# ESP8266_ESP12.net
KiCad netlist of a schematic drawn in Altium Designer
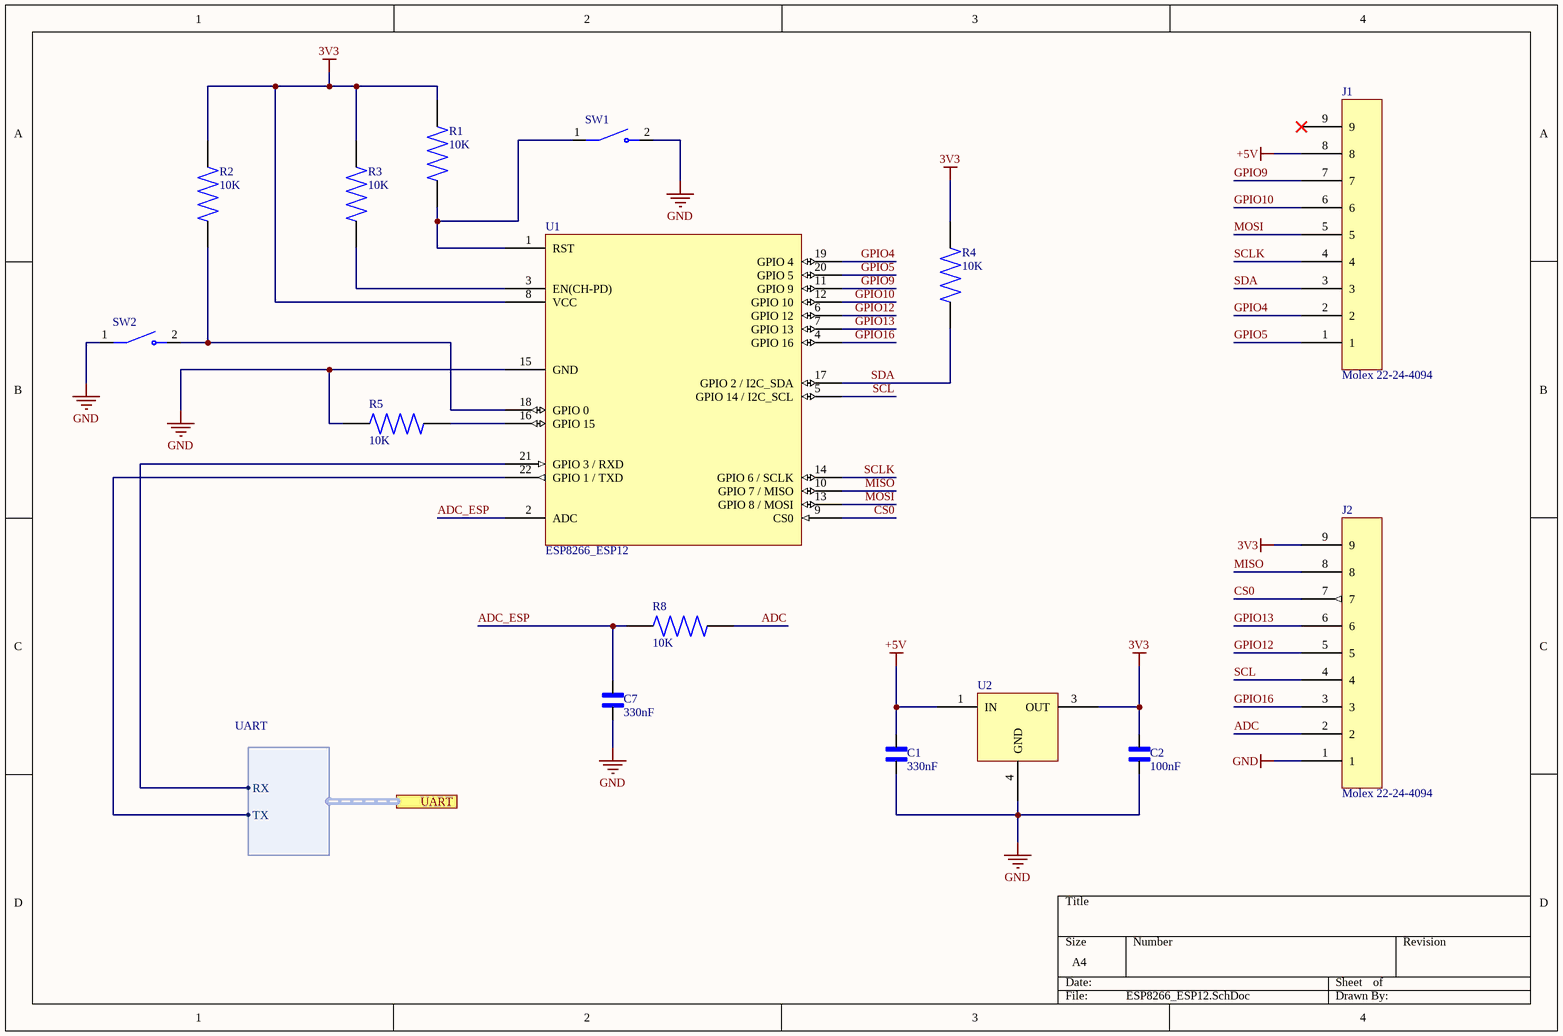
[diagram p0: ESP8266_ESP12.SchDoc]

(export (version "E")
  (design (tool "Eeschema 10.0.6"))
  (components
    (comp (ref "C1")
      (value "330nF")
      (footprint "CAPC1608X90N")
      (fields (field (name "MF") "{'manufacturer': u'Murata'}") (field (name "MP") "GRM188R71C104KA01D"))
      (libsource (lib "*") (part "GRM188R71C104KA01D"))
    )
    (comp (ref "C2")
      (value "100nF")
      (footprint "CAPC1608X90N")
      (fields (field (name "MF") "{'manufacturer': u'Murata'}") (field (name "MP") "GRM188R71C104KA01D"))
      (libsource (lib "*") (part "GRM188R71C104KA01D"))
    )
    (comp (ref "C7")
      (value "330nF")
      (footprint "CAPC1608X90N")
      (fields (field (name "MF") "{'manufacturer': u'Murata'}") (field (name "MP") "GRM188R71C104KA01D"))
      (libsource (lib "*") (part "GRM188R71C104KA01D"))
    )
    (comp (ref "J1")
      (value "Molex 22-24-4094")
      (footprint "Molex 22-28-4094")
      (libsource (lib "") (part "Molex_1"))
    )
    (comp (ref "J2")
      (value "Molex 22-24-4094")
      (footprint "Molex 22-28-4094")
      (libsource (lib "Ala") (part "Molex"))
    )
    (comp (ref "R1")
      (value "10K")
      (footprint "CRCW06032K20FKEA:RESC1508X50N")
      (description "CRCW06032K20FKEA")
      (fields (field (name "MF") "{'manufacturer': u'Vishay Dale'}"))
      (libsource (lib "CRCW06032K20FKEA") (part "CRCW06032K20FKEA"))
    )
    (comp (ref "R2")
      (value "10K")
      (footprint "CRCW06032K20FKEA:RESC1508X50N")
      (description "CRCW06032K20FKEA")
      (fields (field (name "MF") "{'manufacturer': u'Vishay Dale'}"))
      (libsource (lib "CRCW06032K20FKEA") (part "CRCW06032K20FKEA"))
    )
    (comp (ref "R3")
      (value "10K")
      (footprint "CRCW06032K20FKEA:RESC1508X50N")
      (description "CRCW06032K20FKEA")
      (fields (field (name "MF") "{'manufacturer': u'Vishay Dale'}"))
      (libsource (lib "CRCW06032K20FKEA") (part "CRCW06032K20FKEA"))
    )
    (comp (ref "R4")
      (value "10K")
      (footprint "CRCW06032K20FKEA:RESC1508X50N")
      (description "CRCW06032K20FKEA")
      (fields (field (name "MF") "{'manufacturer': u'Vishay Dale'}"))
      (libsource (lib "CRCW06032K20FKEA") (part "CRCW06032K20FKEA"))
    )
    (comp (ref "R5")
      (value "10K")
      (footprint "CRCW06032K20FKEA:RESC1508X50N")
      (description "CRCW06032K20FKEA")
      (fields (field (name "MF") "{'manufacturer': u'Vishay Dale'}"))
      (libsource (lib "CRCW06032K20FKEA") (part "CRCW06032K20FKEA"))
    )
    (comp (ref "R8")
      (value "10K")
      (footprint "CRCW06032K20FKEA:RESC1508X50N")
      (description "CRCW06032K20FKEA")
      (fields (field (name "MF") "{'manufacturer': u'Vishay Dale'}"))
      (libsource (lib "CRCW06032K20FKEA") (part "CRCW06032K20FKEA"))
    )
    (comp (ref "SW1")
      (value "B3U-1000P")
      (footprint "SW_B3U-1000P")
      (description "Switch Tactile N.O. SPST Round Button Gull Wing 0.05A 12VDC 1.5N SMD Embossed T/R")
      (libsource (lib "SW_B3U-1000P") (part "B3U-1000P"))
    )
    (comp (ref "SW2")
      (value "B3U-1000P")
      (footprint "SW_B3U-1000P")
      (description "Switch Tactile N.O. SPST Round Button Gull Wing 0.05A 12VDC 1.5N SMD Embossed T/R")
      (libsource (lib "SW_B3U-1000P") (part "B3U-1000P"))
    )
    (comp (ref "U1")
      (value "ESP8266_ESP12")
      (footprint "ESP8266-ESP12")
      (libsource (lib "Ala") (part "ESP8266_ESP12"))
    )
    (comp (ref "U2")
      (value "UA78M33CDCY")
      (footprint "UA78M33CDCY")
      (description "TI (Texas Instruments) UA78M33CDCY")
      (libsource (lib "Ala") (part "UA78M33CDCY"))
    )
  )
  (nets
    (net (code "2") (name "+5V") (class "Default")
      (node (ref "C1") (pin "2") (pinfunction "2_2") (pintype "passive"))
      (node (ref "J1") (pin "8") (pinfunction "8_8") (pintype "passive"))
      (node (ref "U2") (pin "1") (pinfunction "IN_1") (pintype "passive"))
    )
    (net (code "3") (name "/ADC") (class "Default")
      (node (ref "J2") (pin "2") (pinfunction "2_2") (pintype "passive"))
      (node (ref "R8") (pin "2") (pinfunction "2_2") (pintype "passive"))
    )
    (net (code "4") (name "/ADC_ESP") (class "Default")
      (node (ref "C7") (pin "2") (pinfunction "2_2") (pintype "passive"))
      (node (ref "R8") (pin "1") (pinfunction "1_1") (pintype "passive"))
      (node (ref "U1") (pin "2") (pinfunction "ADC_2") (pintype "passive"))
    )
    (net (code "5") (name "/CS0") (class "Default")
      (node (ref "J2") (pin "7") (pinfunction "7_7") (pintype "output"))
      (node (ref "U1") (pin "9") (pinfunction "CS0_9") (pintype "input"))
    )
    (net (code "6") (name "/GPIO4") (class "Default")
      (node (ref "J1") (pin "2") (pinfunction "2_2") (pintype "passive"))
      (node (ref "U1") (pin "19") (pinfunction "GPIO_4_19") (pintype "bidirectional"))
    )
    (net (code "7") (name "/GPIO5") (class "Default")
      (node (ref "J1") (pin "1") (pinfunction "1_1") (pintype "passive"))
      (node (ref "U1") (pin "20") (pinfunction "GPIO_5_20") (pintype "bidirectional"))
    )
    (net (code "8") (name "/GPIO9") (class "Default")
      (node (ref "J1") (pin "7") (pinfunction "7_7") (pintype "passive"))
      (node (ref "U1") (pin "11") (pinfunction "GPIO_9_11") (pintype "bidirectional"))
    )
    (net (code "9") (name "/GPIO10") (class "Default")
      (node (ref "J1") (pin "6") (pinfunction "6_6") (pintype "passive"))
      (node (ref "U1") (pin "12") (pinfunction "GPIO_10_12") (pintype "bidirectional"))
    )
    (net (code "10") (name "/GPIO12") (class "Default")
      (node (ref "J2") (pin "5") (pinfunction "5_5") (pintype "passive"))
      (node (ref "U1") (pin "6") (pinfunction "GPIO_12_6") (pintype "bidirectional"))
    )
    (net (code "11") (name "/GPIO13") (class "Default")
      (node (ref "J2") (pin "6") (pinfunction "6_6") (pintype "passive"))
      (node (ref "U1") (pin "7") (pinfunction "GPIO_13_7") (pintype "bidirectional"))
    )
    (net (code "12") (name "/GPIO16") (class "Default")
      (node (ref "J2") (pin "3") (pinfunction "3_3") (pintype "passive"))
      (node (ref "U1") (pin "4") (pinfunction "GPIO_16_4") (pintype "bidirectional"))
    )
    (net (code "13") (name "/MISO") (class "Default")
      (node (ref "J2") (pin "8") (pinfunction "8_8") (pintype "passive"))
      (node (ref "U1") (pin "10") (pinfunction "GPIO_7_/_MISO_10") (pintype "bidirectional"))
    )
    (net (code "14") (name "/MOSI") (class "Default")
      (node (ref "J1") (pin "5") (pinfunction "5_5") (pintype "passive"))
      (node (ref "U1") (pin "13") (pinfunction "GPIO_8_/_MOSI_13") (pintype "bidirectional"))
    )
    (net (code "15") (name "/RX") (class "Default")
      (node (ref "U1") (pin "21") (pinfunction "GPIO_3_/_RXD_21") (pintype "input"))
    )
    (net (code "16") (name "/SCL") (class "Default")
      (node (ref "J2") (pin "4") (pinfunction "4_4") (pintype "passive"))
      (node (ref "U1") (pin "5") (pinfunction "GPIO_14_/_I2C_SCL_5") (pintype "bidirectional"))
    )
    (net (code "17") (name "/SCLK") (class "Default")
      (node (ref "J1") (pin "4") (pinfunction "4_4") (pintype "passive"))
      (node (ref "U1") (pin "14") (pinfunction "GPIO_6_/_SCLK_14") (pintype "bidirectional"))
    )
    (net (code "18") (name "/SDA") (class "Default")
      (node (ref "J1") (pin "3") (pinfunction "3_3") (pintype "passive"))
      (node (ref "R4") (pin "1") (pinfunction "1_1") (pintype "passive"))
      (node (ref "U1") (pin "17") (pinfunction "GPIO_2_/_I2C_SDA_17") (pintype "bidirectional"))
    )
    (net (code "20") (name "3V3") (class "Default")
      (node (ref "C2") (pin "2") (pinfunction "2_2") (pintype "passive"))
      (node (ref "J2") (pin "9") (pinfunction "9_9") (pintype "passive"))
      (node (ref "R1") (pin "2") (pinfunction "2_2") (pintype "passive"))
      (node (ref "R2") (pin "2") (pinfunction "2_2") (pintype "passive"))
      (node (ref "R3") (pin "2") (pinfunction "2_2") (pintype "passive"))
      (node (ref "R4") (pin "2") (pinfunction "2_2") (pintype "passive"))
      (node (ref "U1") (pin "8") (pinfunction "VCC_8") (pintype "passive"))
      (node (ref "U2") (pin "3") (pinfunction "OUT_3") (pintype "passive"))
    )
    (net (code "21") (name "GND") (class "Default")
      (node (ref "C1") (pin "1") (pinfunction "1_1") (pintype "passive"))
      (node (ref "C2") (pin "1") (pinfunction "1_1") (pintype "passive"))
      (node (ref "C7") (pin "1") (pinfunction "1_1") (pintype "passive"))
      (node (ref "J2") (pin "1") (pinfunction "1_1") (pintype "passive"))
      (node (ref "R5") (pin "1") (pinfunction "1_1") (pintype "passive"))
      (node (ref "SW1") (pin "2") (pinfunction "2_2") (pintype "passive"))
      (node (ref "SW2") (pin "1") (pinfunction "1_1") (pintype "passive"))
      (node (ref "U1") (pin "15") (pinfunction "GND_15") (pintype "passive"))
      (node (ref "U2") (pin "4") (pinfunction "GND_4") (pintype "passive"))
    )
    (net (code "22") (name "Net-(U1-EN(CH-PD))") (class "Default")
      (node (ref "R3") (pin "1") (pinfunction "1_1") (pintype "passive"))
      (node (ref "U1") (pin "3") (pinfunction "EN(CH-PD)_3") (pintype "passive"))
    )
    (net (code "23") (name "Net-(U1-GPIO_0)") (class "Default")
      (node (ref "R2") (pin "1") (pinfunction "1_1") (pintype "passive"))
      (node (ref "SW2") (pin "2") (pinfunction "2_2") (pintype "passive"))
      (node (ref "U1") (pin "18") (pinfunction "GPIO_0_18") (pintype "bidirectional"))
    )
    (net (code "24") (name "Net-(U1-GPIO_15)") (class "Default")
      (node (ref "R5") (pin "2") (pinfunction "2_2") (pintype "passive"))
      (node (ref "U1") (pin "16") (pinfunction "GPIO_15_16") (pintype "bidirectional"))
    )
    (net (code "25") (name "Net-(U1-RST)") (class "Default")
      (node (ref "R1") (pin "1") (pinfunction "1_1") (pintype "passive"))
      (node (ref "SW1") (pin "1") (pinfunction "1_1") (pintype "passive"))
      (node (ref "U1") (pin "1") (pinfunction "RST_1") (pintype "passive"))
    )
    (net (code "26") (name "unconnected-(J1-Pad9)") (class "Default")
      (node (ref "J1") (pin "9") (pinfunction "9_9") (pintype "passive+no_connect"))
    )
    (net (code "27") (name "unconnected-(U1-GPIO_1_{slash}_TXD-Pad22)") (class "Default")
      (node (ref "U1") (pin "22") (pinfunction "GPIO_1_/_TXD_22") (pintype "output"))
    )
  )
)
